# Daughter_Board.net
KiCad netlist of a schematic drawn in EAGLE
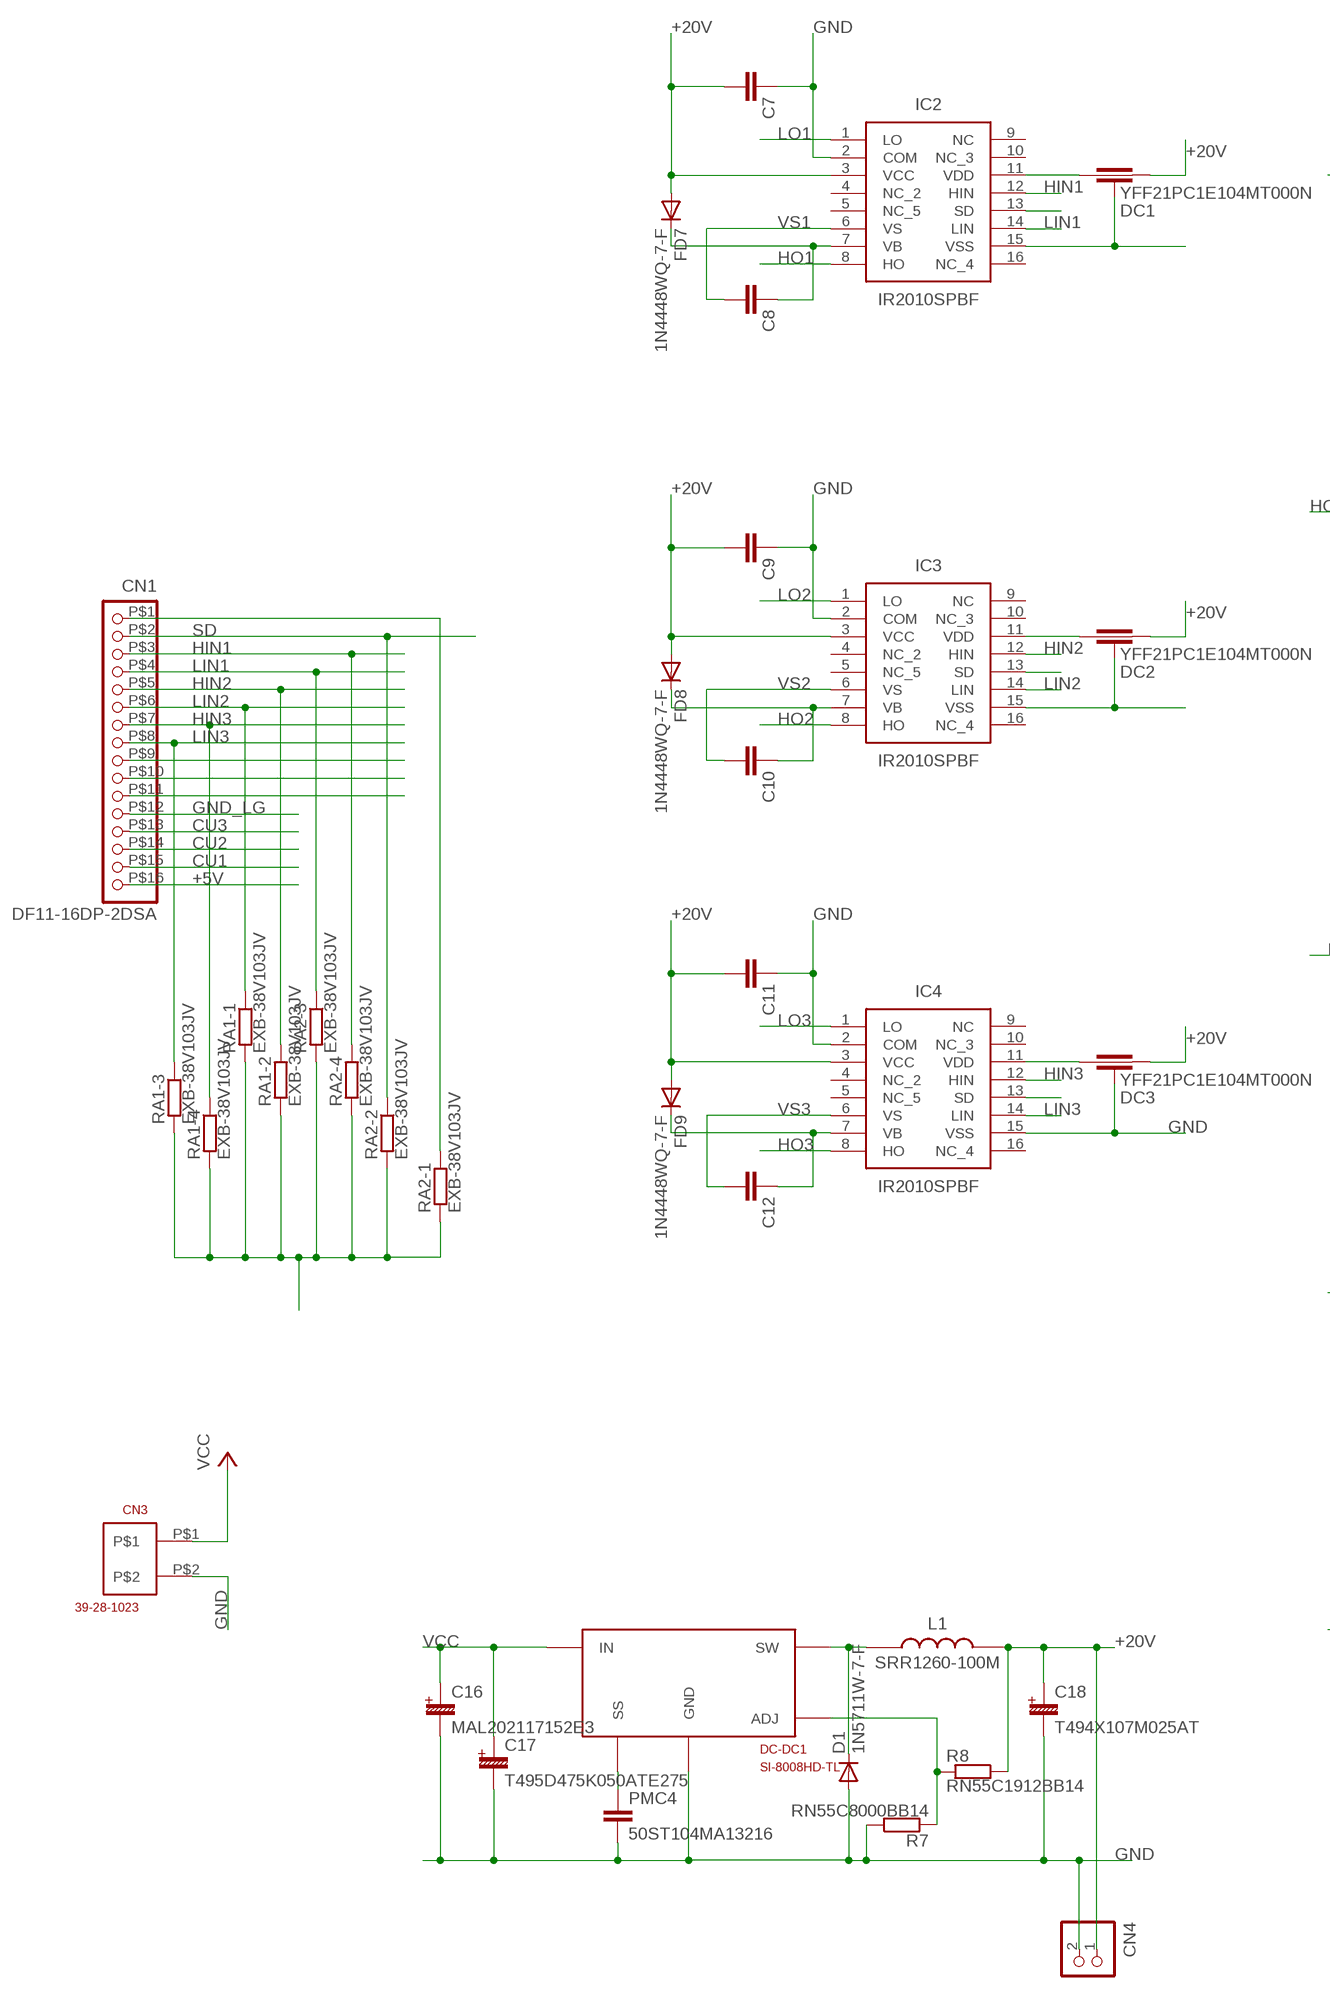
[diagram p0: schematic, sheet 1, part 1 of 3]
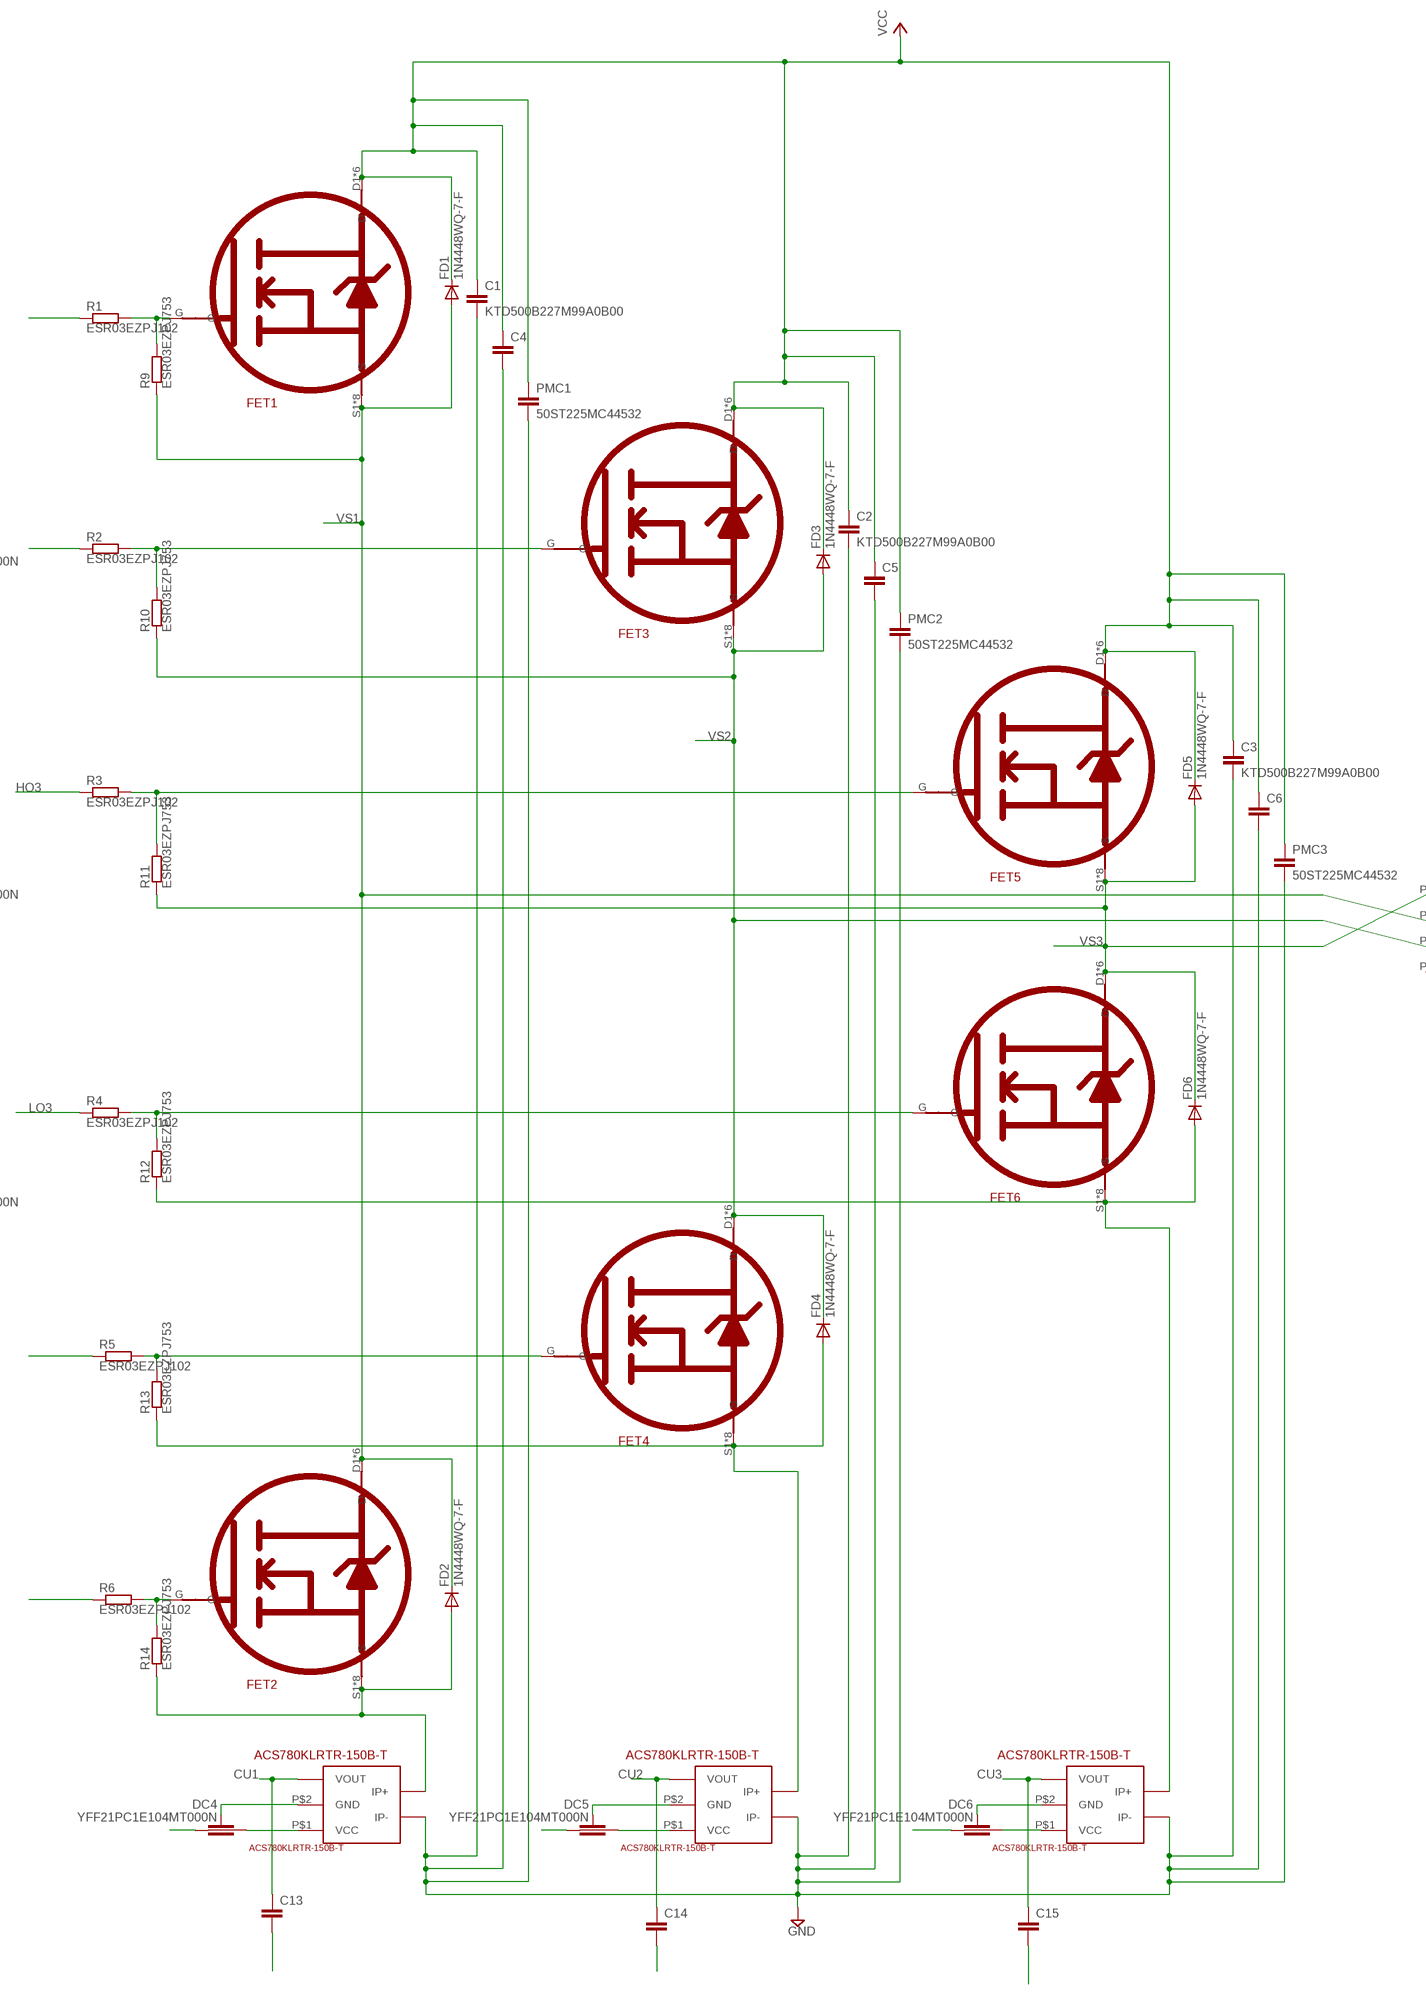
[diagram p1: schematic, sheet 1, part 2 of 3]
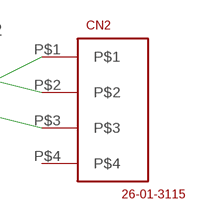
[diagram p2: schematic, sheet 1, part 3 of 3]

(export (version "E")
  (design (tool "Eeschema 10.0.6"))
  (components
    (comp (ref "C1")
      (value "KTD500B227M99A0B00")
      (footprint "eagle-import:TKA50V_150U-220")
      (libsource (lib "eagle-import") (part "KTD500B227M99A0B00"))
    )
    (comp (ref "C2")
      (value "KTD500B227M99A0B00")
      (footprint "eagle-import:TKA50V_150U-220")
      (libsource (lib "eagle-import") (part "KTD500B227M99A0B00"))
    )
    (comp (ref "C3")
      (value "KTD500B227M99A0B00")
      (footprint "eagle-import:TKA50V_150U-220")
      (libsource (lib "eagle-import") (part "KTD500B227M99A0B00"))
    )
    (comp (ref "C4")
      (value "CKG32KX7R1H105M335AJ")
      (footprint "eagle-import:CGK32K")
      (libsource (lib "eagle-import") (part "CKG32KX7R1H105M335AJ"))
    )
    (comp (ref "C5")
      (value "CKG32KX7R1H105M335AJ")
      (footprint "eagle-import:CGK32K")
      (libsource (lib "eagle-import") (part "CKG32KX7R1H105M335AJ"))
    )
    (comp (ref "C6")
      (value "CKG32KX7R1H105M335AJ")
      (footprint "eagle-import:CGK32K")
      (libsource (lib "eagle-import") (part "CKG32KX7R1H105M335AJ"))
    )
    (comp (ref "C7")
      (value "C2012JB0J476M125AC")
      (footprint "eagle-import:C2012")
      (libsource (lib "eagle-import") (part "C2012JB0J476M125AC"))
    )
    (comp (ref "C8")
      (value "C2012JB0J476M125AC")
      (footprint "eagle-import:C2012")
      (libsource (lib "eagle-import") (part "C2012JB0J476M125AC"))
    )
    (comp (ref "C9")
      (value "C2012JB0J476M125AC")
      (footprint "eagle-import:C2012")
      (libsource (lib "eagle-import") (part "C2012JB0J476M125AC"))
    )
    (comp (ref "C10")
      (value "C2012JB0J476M125AC")
      (footprint "eagle-import:C2012")
      (libsource (lib "eagle-import") (part "C2012JB0J476M125AC"))
    )
    (comp (ref "C11")
      (value "C2012JB0J476M125AC")
      (footprint "eagle-import:C2012")
      (libsource (lib "eagle-import") (part "C2012JB0J476M125AC"))
    )
    (comp (ref "C12")
      (value "C2012JB0J476M125AC")
      (footprint "eagle-import:C2012")
      (libsource (lib "eagle-import") (part "C2012JB0J476M125AC"))
    )
    (comp (ref "C13")
      (value "CGA1A2C0G1E180J030BA")
      (footprint "eagle-import:CC0603")
      (libsource (lib "eagle-import") (part "CGA1A2C0G1E180J030BA"))
    )
    (comp (ref "C14")
      (value "CGA1A2C0G1E180J030BA")
      (footprint "eagle-import:CC0603")
      (libsource (lib "eagle-import") (part "CGA1A2C0G1E180J030BA"))
    )
    (comp (ref "C15")
      (value "CGA1A2C0G1E180J030BA")
      (footprint "eagle-import:CC0603")
      (libsource (lib "eagle-import") (part "CGA1A2C0G1E180J030BA"))
    )
    (comp (ref "C16")
      (value "MAL202117152E3")
      (footprint "eagle-import:012AMS13_30")
      (libsource (lib "eagle-import") (part "MAL202117152E3"))
    )
    (comp (ref "C17")
      (value "T495D475K050ATE275")
      (footprint "eagle-import:T495_D")
      (libsource (lib "eagle-import") (part "T495D475K050ATE275"))
    )
    (comp (ref "C18")
      (value "T494X107M025AT")
      (footprint "eagle-import:T494_X")
      (libsource (lib "eagle-import") (part "T494X107M025AT"))
    )
    (comp (ref "CN1")
      (value "DF11-16DP-2DSA")
      (footprint "eagle-import:DF11-16DP-2D")
      (libsource (lib "eagle-import") (part "DF11-16DP-2DSA"))
    )
    (comp (ref "CN2")
      (value "26-01-3115")
      (footprint "eagle-import:26-01-3115")
      (libsource (lib "eagle-import") (part "26-01-3115"))
    )
    (comp (ref "CN3")
      (value "39-28-1023")
      (footprint "eagle-import:39-28-1023")
      (libsource (lib "eagle-import") (part "39-28-1023"))
    )
    (comp (ref "CN4")
      (value "B2B-XH-A")
      (footprint "eagle-import:B2B-XH-A")
      (libsource (lib "eagle-import") (part "B2B-XH-A"))
    )
    (comp (ref "D1")
      (value "1N5711W-7-F")
      (footprint "eagle-import:SOD123")
      (libsource (lib "eagle-import") (part "1N5711W-7-F"))
    )
    (comp (ref "DC-DC1")
      (value "SI-8008HD-TL")
      (footprint "eagle-import:D2_PACAGE_5PIN")
      (libsource (lib "eagle-import") (part "SI-8008HD-TL"))
    )
    (comp (ref "DC1")
      (value "YFF21PC1E104MT000N")
      (footprint "eagle-import:YFF21PC")
      (libsource (lib "eagle-import") (part "YFF21PC1E104MT000N"))
    )
    (comp (ref "DC2")
      (value "YFF21PC1E104MT000N")
      (footprint "eagle-import:YFF21PC")
      (libsource (lib "eagle-import") (part "YFF21PC1E104MT000N"))
    )
    (comp (ref "DC3")
      (value "YFF21PC1E104MT000N")
      (footprint "eagle-import:YFF21PC")
      (libsource (lib "eagle-import") (part "YFF21PC1E104MT000N"))
    )
    (comp (ref "DC4")
      (value "YFF21PC1E104MT000N")
      (footprint "eagle-import:YFF21PC")
      (libsource (lib "eagle-import") (part "YFF21PC1E104MT000N"))
    )
    (comp (ref "DC5")
      (value "YFF21PC1E104MT000N")
      (footprint "eagle-import:YFF21PC")
      (libsource (lib "eagle-import") (part "YFF21PC1E104MT000N"))
    )
    (comp (ref "DC6")
      (value "YFF21PC1E104MT000N")
      (footprint "eagle-import:YFF21PC")
      (libsource (lib "eagle-import") (part "YFF21PC1E104MT000N"))
    )
    (comp (ref "FD1")
      (value "1N4448WQ-7-F")
      (footprint "eagle-import:SOD123")
      (libsource (lib "eagle-import") (part "1N4448WQ-7-F"))
    )
    (comp (ref "FD2")
      (value "1N4448WQ-7-F")
      (footprint "eagle-import:SOD123")
      (libsource (lib "eagle-import") (part "1N4448WQ-7-F"))
    )
    (comp (ref "FD3")
      (value "1N4448WQ-7-F")
      (footprint "eagle-import:SOD123")
      (libsource (lib "eagle-import") (part "1N4448WQ-7-F"))
    )
    (comp (ref "FD4")
      (value "1N4448WQ-7-F")
      (footprint "eagle-import:SOD123")
      (libsource (lib "eagle-import") (part "1N4448WQ-7-F"))
    )
    (comp (ref "FD5")
      (value "1N4448WQ-7-F")
      (footprint "eagle-import:SOD123")
      (libsource (lib "eagle-import") (part "1N4448WQ-7-F"))
    )
    (comp (ref "FD6")
      (value "1N4448WQ-7-F")
      (footprint "eagle-import:SOD123")
      (libsource (lib "eagle-import") (part "1N4448WQ-7-F"))
    )
    (comp (ref "FD7")
      (value "1N4448WQ-7-F")
      (footprint "eagle-import:SOD123")
      (libsource (lib "eagle-import") (part "1N4448WQ-7-F"))
    )
    (comp (ref "FD8")
      (value "1N4448WQ-7-F")
      (footprint "eagle-import:SOD123")
      (libsource (lib "eagle-import") (part "1N4448WQ-7-F"))
    )
    (comp (ref "FD9")
      (value "1N4448WQ-7-F")
      (footprint "eagle-import:SOD123")
      (libsource (lib "eagle-import") (part "1N4448WQ-7-F"))
    )
    (comp (ref "FET1")
      (value "IRF7739L1TRPBF")
      (footprint "eagle-import:DIRECT_FET-L8")
      (libsource (lib "eagle-import") (part "IRF7739L1TRPBF"))
    )
    (comp (ref "FET2")
      (value "IRF7739L1TRPBF")
      (footprint "eagle-import:DIRECT_FET-L8")
      (libsource (lib "eagle-import") (part "IRF7739L1TRPBF"))
    )
    (comp (ref "FET3")
      (value "IRF7739L1TRPBF")
      (footprint "eagle-import:DIRECT_FET-L8")
      (libsource (lib "eagle-import") (part "IRF7739L1TRPBF"))
    )
    (comp (ref "FET4")
      (value "IRF7739L1TRPBF")
      (footprint "eagle-import:DIRECT_FET-L8")
      (libsource (lib "eagle-import") (part "IRF7739L1TRPBF"))
    )
    (comp (ref "FET5")
      (value "IRF7739L1TRPBF")
      (footprint "eagle-import:DIRECT_FET-L8")
      (libsource (lib "eagle-import") (part "IRF7739L1TRPBF"))
    )
    (comp (ref "FET6")
      (value "IRF7739L1TRPBF")
      (footprint "eagle-import:DIRECT_FET-L8")
      (libsource (lib "eagle-import") (part "IRF7739L1TRPBF"))
    )
    (comp (ref "IC1")
      (value "ACS780KLRTR-150B-T")
      (footprint "eagle-import:7-PIN_PSOP")
      (libsource (lib "eagle-import") (part "ACS780KLRTR-150B-T"))
    )
    (comp (ref "IC2")
      (value "IR2010SPBF")
      (footprint "eagle-import:SOIC127P1032X265-16N")
      (fields (field (name "RS_PART_NUMBER") "2509056226"))
      (libsource (lib "eagle-import") (part "IR2010SPBF"))
    )
    (comp (ref "IC3")
      (value "IR2010SPBF")
      (footprint "eagle-import:SOIC127P1032X265-16N")
      (fields (field (name "RS_PART_NUMBER") "2509056226"))
      (libsource (lib "eagle-import") (part "IR2010SPBF"))
    )
    (comp (ref "IC4")
      (value "IR2010SPBF")
      (footprint "eagle-import:SOIC127P1032X265-16N")
      (fields (field (name "RS_PART_NUMBER") "2509056226"))
      (libsource (lib "eagle-import") (part "IR2010SPBF"))
    )
    (comp (ref "IC5")
      (value "ACS780KLRTR-150B-T")
      (footprint "eagle-import:7-PIN_PSOP")
      (libsource (lib "eagle-import") (part "ACS780KLRTR-150B-T"))
    )
    (comp (ref "IC6")
      (value "ACS780KLRTR-150B-T")
      (footprint "eagle-import:7-PIN_PSOP")
      (libsource (lib "eagle-import") (part "ACS780KLRTR-150B-T"))
    )
    (comp (ref "L1")
      (value "SRR1260-100M")
      (footprint "eagle-import:SRR1260")
      (libsource (lib "eagle-import") (part "SRR1260-100M"))
    )
    (comp (ref "PMC1")
      (value "50ST225MC44532")
      (footprint "eagle-import:4532")
      (libsource (lib "eagle-import") (part "50ST225MC44532"))
    )
    (comp (ref "PMC2")
      (value "50ST225MC44532")
      (footprint "eagle-import:4532")
      (libsource (lib "eagle-import") (part "50ST225MC44532"))
    )
    (comp (ref "PMC3")
      (value "50ST225MC44532")
      (footprint "eagle-import:4532")
      (libsource (lib "eagle-import") (part "50ST225MC44532"))
    )
    (comp (ref "PMC4")
      (value "50ST104MA13216")
      (footprint "eagle-import:3216")
      (libsource (lib "eagle-import") (part "50ST104MA13216"))
    )
    (comp (ref "R1")
      (value "ESR03EZPJ102")
      (footprint "eagle-import:ESR03")
      (libsource (lib "eagle-import") (part "ESR03EZPJ102"))
    )
    (comp (ref "R2")
      (value "ESR03EZPJ102")
      (footprint "eagle-import:ESR03")
      (libsource (lib "eagle-import") (part "ESR03EZPJ102"))
    )
    (comp (ref "R3")
      (value "ESR03EZPJ102")
      (footprint "eagle-import:ESR03")
      (libsource (lib "eagle-import") (part "ESR03EZPJ102"))
    )
    (comp (ref "R4")
      (value "ESR03EZPJ102")
      (footprint "eagle-import:ESR03")
      (libsource (lib "eagle-import") (part "ESR03EZPJ102"))
    )
    (comp (ref "R5")
      (value "ESR03EZPJ102")
      (footprint "eagle-import:ESR03")
      (libsource (lib "eagle-import") (part "ESR03EZPJ102"))
    )
    (comp (ref "R6")
      (value "ESR03EZPJ102")
      (footprint "eagle-import:ESR03")
      (libsource (lib "eagle-import") (part "ESR03EZPJ102"))
    )
    (comp (ref "R7")
      (value "RN55C8000BB14")
      (footprint "eagle-import:CMF55")
      (libsource (lib "eagle-import") (part "RN55C8000BB14"))
    )
    (comp (ref "R8")
      (value "RN55C1912BB14")
      (footprint "eagle-import:CMF55")
      (libsource (lib "eagle-import") (part "RN55C1912BB14"))
    )
    (comp (ref "R9")
      (value "ESR03EZPJ753")
      (footprint "eagle-import:ESR03")
      (libsource (lib "eagle-import") (part "ESR03EZPJ753"))
    )
    (comp (ref "R10")
      (value "ESR03EZPJ753")
      (footprint "eagle-import:ESR03")
      (libsource (lib "eagle-import") (part "ESR03EZPJ753"))
    )
    (comp (ref "R11")
      (value "ESR03EZPJ753")
      (footprint "eagle-import:ESR03")
      (libsource (lib "eagle-import") (part "ESR03EZPJ753"))
    )
    (comp (ref "R12")
      (value "ESR03EZPJ753")
      (footprint "eagle-import:ESR03")
      (libsource (lib "eagle-import") (part "ESR03EZPJ753"))
    )
    (comp (ref "R13")
      (value "ESR03EZPJ753")
      (footprint "eagle-import:ESR03")
      (libsource (lib "eagle-import") (part "ESR03EZPJ753"))
    )
    (comp (ref "R14")
      (value "ESR03EZPJ753")
      (footprint "eagle-import:ESR03")
      (libsource (lib "eagle-import") (part "ESR03EZPJ753"))
    )
    (comp (ref "RA1")
      (value "EXB-38V103JV")
      (footprint "eagle-import:EXB-38V,28V")
      (libsource (lib "eagle-import") (part "EXB-38V103JV"))
    )
    (comp (ref "RA2")
      (value "EXB-38V103JV")
      (footprint "eagle-import:EXB-38V,28V")
      (libsource (lib "eagle-import") (part "EXB-38V103JV"))
    )
  )
  (nets
    (net (code "1") (name "/+5V") (class "Default")
      (node (ref "CN1") (pin "P$16") (pinfunction "16_P$16") (pintype "passive"))
      (node (ref "DC4") (pin "P$2") (pinfunction "P$2_P$2") (pintype "bidirectional"))
      (node (ref "DC5") (pin "P$2") (pinfunction "P$2_P$2") (pintype "bidirectional"))
      (node (ref "DC6") (pin "P$2") (pinfunction "P$2_P$2") (pintype "bidirectional"))
    )
    (net (code "2") (name "/+20V") (class "Default")
      (node (ref "C11") (pin "P$2") (pinfunction "2_P$2") (pintype "passive"))
      (node (ref "C18") (pin "P$+") (pinfunction "+_P$+") (pintype "passive"))
      (node (ref "C7") (pin "P$2") (pinfunction "2_P$2") (pintype "passive"))
      (node (ref "C9") (pin "P$2") (pinfunction "2_P$2") (pintype "passive"))
      (node (ref "CN4") (pin "1") (pinfunction "1_1") (pintype "passive"))
      (node (ref "DC1") (pin "P$2") (pinfunction "P$2_P$2") (pintype "bidirectional"))
      (node (ref "DC2") (pin "P$2") (pinfunction "P$2_P$2") (pintype "bidirectional"))
      (node (ref "DC3") (pin "P$2") (pinfunction "P$2_P$2") (pintype "bidirectional"))
      (node (ref "FD7") (pin "A") (pinfunction "A_A") (pintype "passive"))
      (node (ref "FD8") (pin "A") (pinfunction "A_A") (pintype "passive"))
      (node (ref "FD9") (pin "A") (pinfunction "A_A") (pintype "passive"))
      (node (ref "IC2") (pin "3") (pinfunction "VCC_3") (pintype "passive"))
      (node (ref "IC3") (pin "3") (pinfunction "VCC_3") (pintype "passive"))
      (node (ref "IC4") (pin "3") (pinfunction "VCC_3") (pintype "passive"))
      (node (ref "L1") (pin "P$2") (pinfunction "2_P$2") (pintype "bidirectional"))
      (node (ref "R8") (pin "P$1") (pinfunction "1_P$1") (pintype "passive"))
    )
    (net (code "3") (name "/CU1") (class "Default")
      (node (ref "C13") (pin "P$1") (pinfunction "1_P$1") (pintype "passive"))
      (node (ref "CN1") (pin "P$15") (pinfunction "15_P$15") (pintype "passive"))
      (node (ref "IC1") (pin "P$3") (pinfunction "VOUT_P$3") (pintype "bidirectional"))
    )
    (net (code "4") (name "/CU2") (class "Default")
      (node (ref "C14") (pin "P$1") (pinfunction "1_P$1") (pintype "passive"))
      (node (ref "CN1") (pin "P$14") (pinfunction "14_P$14") (pintype "passive"))
      (node (ref "IC5") (pin "P$3") (pinfunction "VOUT_P$3") (pintype "bidirectional"))
    )
    (net (code "5") (name "/CU3") (class "Default")
      (node (ref "C15") (pin "P$1") (pinfunction "1_P$1") (pintype "passive"))
      (node (ref "CN1") (pin "P$13") (pinfunction "13_P$13") (pintype "passive"))
      (node (ref "IC6") (pin "P$3") (pinfunction "VOUT_P$3") (pintype "bidirectional"))
    )
    (net (code "6") (name "/GND_LG") (class "Default")
      (node (ref "C13") (pin "P$2") (pinfunction "2_P$2") (pintype "passive"))
      (node (ref "C14") (pin "P$2") (pinfunction "2_P$2") (pintype "passive"))
      (node (ref "C15") (pin "P$2") (pinfunction "2_P$2") (pintype "passive"))
      (node (ref "CN1") (pin "P$12") (pinfunction "12_P$12") (pintype "passive"))
      (node (ref "DC4") (pin "GND1") (pinfunction "GND_GND1") (pintype "bidirectional"))
      (node (ref "DC4") (pin "GND2") (pinfunction "GND_GND2") (pintype "bidirectional"))
      (node (ref "DC5") (pin "GND1") (pinfunction "GND_GND1") (pintype "bidirectional"))
      (node (ref "DC5") (pin "GND2") (pinfunction "GND_GND2") (pintype "bidirectional"))
      (node (ref "DC6") (pin "GND1") (pinfunction "GND_GND1") (pintype "bidirectional"))
      (node (ref "DC6") (pin "GND2") (pinfunction "GND_GND2") (pintype "bidirectional"))
      (node (ref "IC1") (pin "P$2") (pinfunction "GND_P$2") (pintype "bidirectional"))
      (node (ref "IC5") (pin "P$2") (pinfunction "GND_P$2") (pintype "bidirectional"))
      (node (ref "IC6") (pin "P$2") (pinfunction "GND_P$2") (pintype "bidirectional"))
      (node (ref "RA1") (pin "P$5") (pinfunction "2_P$5") (pintype "passive"))
      (node (ref "RA1") (pin "P$6") (pinfunction "2_P$6") (pintype "passive"))
      (node (ref "RA1") (pin "P$7") (pinfunction "2_P$7") (pintype "passive"))
      (node (ref "RA1") (pin "P$8") (pinfunction "2_P$8") (pintype "passive"))
      (node (ref "RA2") (pin "P$5") (pinfunction "2_P$5") (pintype "passive"))
      (node (ref "RA2") (pin "P$6") (pinfunction "2_P$6") (pintype "passive"))
      (node (ref "RA2") (pin "P$7") (pinfunction "2_P$7") (pintype "passive"))
      (node (ref "RA2") (pin "P$8") (pinfunction "2_P$8") (pintype "passive"))
    )
    (net (code "7") (name "/HIN1") (class "Default")
      (node (ref "CN1") (pin "P$3") (pinfunction "3_P$3") (pintype "passive"))
      (node (ref "IC2") (pin "12") (pinfunction "HIN_12") (pintype "passive"))
      (node (ref "RA2") (pin "P$4") (pinfunction "1_P$4") (pintype "passive"))
    )
    (net (code "8") (name "/HIN2") (class "Default")
      (node (ref "CN1") (pin "P$5") (pinfunction "5_P$5") (pintype "passive"))
      (node (ref "IC3") (pin "12") (pinfunction "HIN_12") (pintype "passive"))
      (node (ref "RA1") (pin "P$2") (pinfunction "1_P$2") (pintype "passive"))
    )
    (net (code "9") (name "/HIN3") (class "Default")
      (node (ref "CN1") (pin "P$7") (pinfunction "7_P$7") (pintype "passive"))
      (node (ref "IC4") (pin "12") (pinfunction "HIN_12") (pintype "passive"))
      (node (ref "RA1") (pin "P$4") (pinfunction "1_P$4") (pintype "passive"))
    )
    (net (code "10") (name "/HO1") (class "Default")
      (node (ref "IC2") (pin "8") (pinfunction "HO_8") (pintype "passive"))
      (node (ref "R1") (pin "P$2") (pinfunction "2_P$2") (pintype "passive"))
    )
    (net (code "11") (name "/HO2") (class "Default")
      (node (ref "IC3") (pin "8") (pinfunction "HO_8") (pintype "passive"))
      (node (ref "R2") (pin "P$2") (pinfunction "2_P$2") (pintype "passive"))
    )
    (net (code "12") (name "/HO3") (class "Default")
      (node (ref "IC4") (pin "8") (pinfunction "HO_8") (pintype "passive"))
      (node (ref "R3") (pin "P$2") (pinfunction "2_P$2") (pintype "passive"))
    )
    (net (code "13") (name "/LIN1") (class "Default")
      (node (ref "CN1") (pin "P$4") (pinfunction "4_P$4") (pintype "passive"))
      (node (ref "IC2") (pin "14") (pinfunction "LIN_14") (pintype "passive"))
      (node (ref "RA2") (pin "P$3") (pinfunction "1_P$3") (pintype "passive"))
    )
    (net (code "14") (name "/LIN2") (class "Default")
      (node (ref "CN1") (pin "P$6") (pinfunction "6_P$6") (pintype "passive"))
      (node (ref "IC3") (pin "14") (pinfunction "LIN_14") (pintype "passive"))
      (node (ref "RA1") (pin "P$1") (pinfunction "1_P$1") (pintype "passive"))
    )
    (net (code "15") (name "/LIN3") (class "Default")
      (node (ref "CN1") (pin "P$8") (pinfunction "8_P$8") (pintype "passive"))
      (node (ref "IC4") (pin "14") (pinfunction "LIN_14") (pintype "passive"))
      (node (ref "RA1") (pin "P$3") (pinfunction "1_P$3") (pintype "passive"))
    )
    (net (code "16") (name "/LO1") (class "Default")
      (node (ref "IC2") (pin "1") (pinfunction "LO_1") (pintype "passive"))
      (node (ref "R6") (pin "P$2") (pinfunction "2_P$2") (pintype "passive"))
    )
    (net (code "17") (name "/LO2") (class "Default")
      (node (ref "IC3") (pin "1") (pinfunction "LO_1") (pintype "passive"))
      (node (ref "R5") (pin "P$2") (pinfunction "2_P$2") (pintype "passive"))
    )
    (net (code "18") (name "/LO3") (class "Default")
      (node (ref "IC4") (pin "1") (pinfunction "LO_1") (pintype "passive"))
      (node (ref "R4") (pin "P$2") (pinfunction "2_P$2") (pintype "passive"))
    )
    (net (code "19") (name "/SD") (class "Default")
      (node (ref "CN1") (pin "P$2") (pinfunction "2_P$2") (pintype "passive"))
      (node (ref "IC2") (pin "13") (pinfunction "SD_13") (pintype "passive"))
      (node (ref "IC3") (pin "13") (pinfunction "SD_13") (pintype "passive"))
      (node (ref "IC4") (pin "13") (pinfunction "SD_13") (pintype "passive"))
      (node (ref "RA2") (pin "P$2") (pinfunction "1_P$2") (pintype "passive"))
    )
    (net (code "20") (name "/VS1") (class "Default")
      (node (ref "C8") (pin "P$2") (pinfunction "2_P$2") (pintype "passive"))
      (node (ref "CN2") (pin "P$2") (pinfunction "P$2_P$2") (pintype "bidirectional"))
      (node (ref "FD1") (pin "A") (pinfunction "A_A") (pintype "passive"))
      (node (ref "FD2") (pin "K") (pinfunction "C_K") (pintype "passive"))
      (node (ref "FET1") (pin "S1") (pinfunction "S_S1") (pintype "bidirectional"))
      (node (ref "FET1") (pin "S2") (pinfunction "S_S2") (pintype "bidirectional"))
      (node (ref "FET1") (pin "S3") (pinfunction "S_S3") (pintype "bidirectional"))
      (node (ref "FET1") (pin "S4") (pinfunction "S_S4") (pintype "bidirectional"))
      (node (ref "FET1") (pin "S5") (pinfunction "S_S5") (pintype "bidirectional"))
      (node (ref "FET1") (pin "S6") (pinfunction "S_S6") (pintype "bidirectional"))
      (node (ref "FET1") (pin "S7") (pinfunction "S_S7") (pintype "bidirectional"))
      (node (ref "FET1") (pin "S8") (pinfunction "S_S8") (pintype "bidirectional"))
      (node (ref "FET2") (pin "D1") (pinfunction "D_D1") (pintype "bidirectional"))
      (node (ref "FET2") (pin "D2") (pinfunction "D_D2") (pintype "bidirectional"))
      (node (ref "FET2") (pin "D3") (pinfunction "D_D3") (pintype "bidirectional"))
      (node (ref "FET2") (pin "D4") (pinfunction "D_D4") (pintype "bidirectional"))
      (node (ref "FET2") (pin "D5") (pinfunction "D_D5") (pintype "bidirectional"))
      (node (ref "FET2") (pin "D6") (pinfunction "D_D6") (pintype "bidirectional"))
      (node (ref "IC2") (pin "6") (pinfunction "VS_6") (pintype "passive"))
      (node (ref "R9") (pin "P$2") (pinfunction "2_P$2") (pintype "passive"))
    )
    (net (code "21") (name "/VS2") (class "Default")
      (node (ref "C10") (pin "P$2") (pinfunction "2_P$2") (pintype "passive"))
      (node (ref "CN2") (pin "P$3") (pinfunction "P$3_P$3") (pintype "bidirectional"))
      (node (ref "FD3") (pin "A") (pinfunction "A_A") (pintype "passive"))
      (node (ref "FD4") (pin "K") (pinfunction "C_K") (pintype "passive"))
      (node (ref "FET3") (pin "S1") (pinfunction "S_S1") (pintype "bidirectional"))
      (node (ref "FET3") (pin "S2") (pinfunction "S_S2") (pintype "bidirectional"))
      (node (ref "FET3") (pin "S3") (pinfunction "S_S3") (pintype "bidirectional"))
      (node (ref "FET3") (pin "S4") (pinfunction "S_S4") (pintype "bidirectional"))
      (node (ref "FET3") (pin "S5") (pinfunction "S_S5") (pintype "bidirectional"))
      (node (ref "FET3") (pin "S6") (pinfunction "S_S6") (pintype "bidirectional"))
      (node (ref "FET3") (pin "S7") (pinfunction "S_S7") (pintype "bidirectional"))
      (node (ref "FET3") (pin "S8") (pinfunction "S_S8") (pintype "bidirectional"))
      (node (ref "FET4") (pin "D1") (pinfunction "D_D1") (pintype "bidirectional"))
      (node (ref "FET4") (pin "D2") (pinfunction "D_D2") (pintype "bidirectional"))
      (node (ref "FET4") (pin "D3") (pinfunction "D_D3") (pintype "bidirectional"))
      (node (ref "FET4") (pin "D4") (pinfunction "D_D4") (pintype "bidirectional"))
      (node (ref "FET4") (pin "D5") (pinfunction "D_D5") (pintype "bidirectional"))
      (node (ref "FET4") (pin "D6") (pinfunction "D_D6") (pintype "bidirectional"))
      (node (ref "IC3") (pin "6") (pinfunction "VS_6") (pintype "passive"))
      (node (ref "R10") (pin "P$2") (pinfunction "2_P$2") (pintype "passive"))
    )
    (net (code "22") (name "/VS3") (class "Default")
      (node (ref "C12") (pin "P$2") (pinfunction "2_P$2") (pintype "passive"))
      (node (ref "CN2") (pin "P$1") (pinfunction "P$1_P$1") (pintype "bidirectional"))
      (node (ref "FD5") (pin "A") (pinfunction "A_A") (pintype "passive"))
      (node (ref "FD6") (pin "K") (pinfunction "C_K") (pintype "passive"))
      (node (ref "FET5") (pin "S1") (pinfunction "S_S1") (pintype "bidirectional"))
      (node (ref "FET5") (pin "S2") (pinfunction "S_S2") (pintype "bidirectional"))
      (node (ref "FET5") (pin "S3") (pinfunction "S_S3") (pintype "bidirectional"))
      (node (ref "FET5") (pin "S4") (pinfunction "S_S4") (pintype "bidirectional"))
      (node (ref "FET5") (pin "S5") (pinfunction "S_S5") (pintype "bidirectional"))
      (node (ref "FET5") (pin "S6") (pinfunction "S_S6") (pintype "bidirectional"))
      (node (ref "FET5") (pin "S7") (pinfunction "S_S7") (pintype "bidirectional"))
      (node (ref "FET5") (pin "S8") (pinfunction "S_S8") (pintype "bidirectional"))
      (node (ref "FET6") (pin "D1") (pinfunction "D_D1") (pintype "bidirectional"))
      (node (ref "FET6") (pin "D2") (pinfunction "D_D2") (pintype "bidirectional"))
      (node (ref "FET6") (pin "D3") (pinfunction "D_D3") (pintype "bidirectional"))
      (node (ref "FET6") (pin "D4") (pinfunction "D_D4") (pintype "bidirectional"))
      (node (ref "FET6") (pin "D5") (pinfunction "D_D5") (pintype "bidirectional"))
      (node (ref "FET6") (pin "D6") (pinfunction "D_D6") (pintype "bidirectional"))
      (node (ref "IC4") (pin "6") (pinfunction "VS_6") (pintype "passive"))
      (node (ref "R11") (pin "P$2") (pinfunction "2_P$2") (pintype "passive"))
    )
    (net (code "23") (name "GND") (class "Default")
      (node (ref "C1") (pin "P$2") (pinfunction "2_P$2") (pintype "passive"))
      (node (ref "C11") (pin "P$1") (pinfunction "1_P$1") (pintype "passive"))
      (node (ref "C16") (pin "P$2") (pinfunction "2_P$2") (pintype "passive"))
      (node (ref "C17") (pin "P$2") (pinfunction "2_P$2") (pintype "passive"))
      (node (ref "C18") (pin "P$2") (pinfunction "2_P$2") (pintype "passive"))
      (node (ref "C2") (pin "P$2") (pinfunction "2_P$2") (pintype "passive"))
      (node (ref "C3") (pin "P$2") (pinfunction "2_P$2") (pintype "passive"))
      (node (ref "C4") (pin "P$2") (pinfunction "2_P$2") (pintype "passive"))
      (node (ref "C5") (pin "P$2") (pinfunction "2_P$2") (pintype "passive"))
      (node (ref "C6") (pin "P$2") (pinfunction "2_P$2") (pintype "passive"))
      (node (ref "C7") (pin "P$1") (pinfunction "1_P$1") (pintype "passive"))
      (node (ref "C9") (pin "P$1") (pinfunction "1_P$1") (pintype "passive"))
      (node (ref "CN3") (pin "P$2") (pinfunction "P$2_P$2") (pintype "bidirectional"))
      (node (ref "CN4") (pin "2") (pinfunction "2_2") (pintype "passive"))
      (node (ref "D1") (pin "A") (pinfunction "A_A") (pintype "passive"))
      (node (ref "DC-DC1") (pin "P$1") (pinfunction "GND_P$1") (pintype "bidirectional"))
      (node (ref "DC-DC1") (pin "P$4") (pinfunction "GND_P$4") (pintype "bidirectional"))
      (node (ref "DC1") (pin "GND1") (pinfunction "GND_GND1") (pintype "bidirectional"))
      (node (ref "DC1") (pin "GND2") (pinfunction "GND_GND2") (pintype "bidirectional"))
      (node (ref "DC2") (pin "GND1") (pinfunction "GND_GND1") (pintype "bidirectional"))
      (node (ref "DC2") (pin "GND2") (pinfunction "GND_GND2") (pintype "bidirectional"))
      (node (ref "DC3") (pin "GND1") (pinfunction "GND_GND1") (pintype "bidirectional"))
      (node (ref "DC3") (pin "GND2") (pinfunction "GND_GND2") (pintype "bidirectional"))
      (node (ref "IC1") (pin "P$6") (pinfunction "IP-_P$6") (pintype "bidirectional"))
      (node (ref "IC2") (pin "15") (pinfunction "VSS_15") (pintype "passive"))
      (node (ref "IC2") (pin "2") (pinfunction "COM_2") (pintype "passive"))
      (node (ref "IC3") (pin "15") (pinfunction "VSS_15") (pintype "passive"))
      (node (ref "IC3") (pin "2") (pinfunction "COM_2") (pintype "passive"))
      (node (ref "IC4") (pin "15") (pinfunction "VSS_15") (pintype "passive"))
      (node (ref "IC4") (pin "2") (pinfunction "COM_2") (pintype "passive"))
      (node (ref "IC5") (pin "P$6") (pinfunction "IP-_P$6") (pintype "bidirectional"))
      (node (ref "IC6") (pin "P$6") (pinfunction "IP-_P$6") (pintype "bidirectional"))
      (node (ref "PMC1") (pin "P$2") (pinfunction "2_P$2") (pintype "passive"))
      (node (ref "PMC2") (pin "P$2") (pinfunction "2_P$2") (pintype "passive"))
      (node (ref "PMC3") (pin "P$2") (pinfunction "2_P$2") (pintype "passive"))
      (node (ref "PMC4") (pin "P$2") (pinfunction "2_P$2") (pintype "passive"))
      (node (ref "R7") (pin "P$1") (pinfunction "1_P$1") (pintype "passive"))
    )
    (net (code "24") (name "Net-(C8-1)") (class "Default")
      (node (ref "C8") (pin "P$1") (pinfunction "1_P$1") (pintype "passive"))
      (node (ref "FD7") (pin "K") (pinfunction "C_K") (pintype "passive"))
      (node (ref "IC2") (pin "7") (pinfunction "VB_7") (pintype "passive"))
    )
    (net (code "25") (name "Net-(C10-1)") (class "Default")
      (node (ref "C10") (pin "P$1") (pinfunction "1_P$1") (pintype "passive"))
      (node (ref "FD8") (pin "K") (pinfunction "C_K") (pintype "passive"))
      (node (ref "IC3") (pin "7") (pinfunction "VB_7") (pintype "passive"))
    )
    (net (code "26") (name "Net-(C12-1)") (class "Default")
      (node (ref "C12") (pin "P$1") (pinfunction "1_P$1") (pintype "passive"))
      (node (ref "FD9") (pin "K") (pinfunction "C_K") (pintype "passive"))
      (node (ref "IC4") (pin "7") (pinfunction "VB_7") (pintype "passive"))
    )
    (net (code "27") (name "Net-(CN1-1)") (class "Default")
      (node (ref "CN1") (pin "P$1") (pinfunction "1_P$1") (pintype "passive"))
      (node (ref "RA2") (pin "P$1") (pinfunction "1_P$1") (pintype "passive"))
    )
    (net (code "28") (name "Net-(D1-C)") (class "Default")
      (node (ref "D1") (pin "K") (pinfunction "C_K") (pintype "passive"))
      (node (ref "DC-DC1") (pin "P$3") (pinfunction "SW_P$3") (pintype "bidirectional"))
      (node (ref "L1") (pin "P$1") (pinfunction "1_P$1") (pintype "bidirectional"))
    )
    (net (code "29") (name "Net-(DC-DC1-ADJ)") (class "Default")
      (node (ref "DC-DC1") (pin "P$5") (pinfunction "ADJ_P$5") (pintype "bidirectional"))
      (node (ref "R7") (pin "P$2") (pinfunction "2_P$2") (pintype "passive"))
      (node (ref "R8") (pin "P$2") (pinfunction "2_P$2") (pintype "passive"))
    )
    (net (code "30") (name "Net-(DC-DC1-SS)") (class "Default")
      (node (ref "DC-DC1") (pin "P$6") (pinfunction "SS_P$6") (pintype "bidirectional"))
      (node (ref "PMC4") (pin "P$1") (pinfunction "1_P$1") (pintype "passive"))
    )
    (net (code "31") (name "Net-(IC1-IP+)") (class "Default")
      (node (ref "FD2") (pin "A") (pinfunction "A_A") (pintype "passive"))
      (node (ref "FET2") (pin "S1") (pinfunction "S_S1") (pintype "bidirectional"))
      (node (ref "FET2") (pin "S2") (pinfunction "S_S2") (pintype "bidirectional"))
      (node (ref "FET2") (pin "S3") (pinfunction "S_S3") (pintype "bidirectional"))
      (node (ref "FET2") (pin "S4") (pinfunction "S_S4") (pintype "bidirectional"))
      (node (ref "FET2") (pin "S5") (pinfunction "S_S5") (pintype "bidirectional"))
      (node (ref "FET2") (pin "S6") (pinfunction "S_S6") (pintype "bidirectional"))
      (node (ref "FET2") (pin "S7") (pinfunction "S_S7") (pintype "bidirectional"))
      (node (ref "FET2") (pin "S8") (pinfunction "S_S8") (pintype "bidirectional"))
      (node (ref "IC1") (pin "P$5") (pinfunction "IP+_P$5") (pintype "bidirectional"))
      (node (ref "R14") (pin "P$2") (pinfunction "2_P$2") (pintype "passive"))
    )
    (net (code "32") (name "Net-(IC1-VCC)") (class "Default")
      (node (ref "DC4") (pin "P$1") (pinfunction "P$1_P$1") (pintype "bidirectional"))
      (node (ref "IC1") (pin "P$1") (pinfunction "VCC_P$1") (pintype "bidirectional"))
    )
    (net (code "33") (name "Net-(IC2-VDD)") (class "Default")
      (node (ref "DC1") (pin "P$1") (pinfunction "P$1_P$1") (pintype "bidirectional"))
      (node (ref "IC2") (pin "11") (pinfunction "VDD_11") (pintype "passive"))
    )
    (net (code "34") (name "Net-(IC3-VDD)") (class "Default")
      (node (ref "DC2") (pin "P$1") (pinfunction "P$1_P$1") (pintype "bidirectional"))
      (node (ref "IC3") (pin "11") (pinfunction "VDD_11") (pintype "passive"))
    )
    (net (code "35") (name "Net-(IC4-VDD)") (class "Default")
      (node (ref "DC3") (pin "P$1") (pinfunction "P$1_P$1") (pintype "bidirectional"))
      (node (ref "IC4") (pin "11") (pinfunction "VDD_11") (pintype "passive"))
    )
    (net (code "36") (name "Net-(IC5-IP+)") (class "Default")
      (node (ref "FD4") (pin "A") (pinfunction "A_A") (pintype "passive"))
      (node (ref "FET4") (pin "S1") (pinfunction "S_S1") (pintype "bidirectional"))
      (node (ref "FET4") (pin "S2") (pinfunction "S_S2") (pintype "bidirectional"))
      (node (ref "FET4") (pin "S3") (pinfunction "S_S3") (pintype "bidirectional"))
      (node (ref "FET4") (pin "S4") (pinfunction "S_S4") (pintype "bidirectional"))
      (node (ref "FET4") (pin "S5") (pinfunction "S_S5") (pintype "bidirectional"))
      (node (ref "FET4") (pin "S6") (pinfunction "S_S6") (pintype "bidirectional"))
      (node (ref "FET4") (pin "S7") (pinfunction "S_S7") (pintype "bidirectional"))
      (node (ref "FET4") (pin "S8") (pinfunction "S_S8") (pintype "bidirectional"))
      (node (ref "IC5") (pin "P$5") (pinfunction "IP+_P$5") (pintype "bidirectional"))
      (node (ref "R13") (pin "P$2") (pinfunction "2_P$2") (pintype "passive"))
    )
    (net (code "37") (name "Net-(IC5-VCC)") (class "Default")
      (node (ref "DC5") (pin "P$1") (pinfunction "P$1_P$1") (pintype "bidirectional"))
      (node (ref "IC5") (pin "P$1") (pinfunction "VCC_P$1") (pintype "bidirectional"))
    )
    (net (code "38") (name "Net-(IC6-IP+)") (class "Default")
      (node (ref "FD6") (pin "A") (pinfunction "A_A") (pintype "passive"))
      (node (ref "FET6") (pin "S1") (pinfunction "S_S1") (pintype "bidirectional"))
      (node (ref "FET6") (pin "S2") (pinfunction "S_S2") (pintype "bidirectional"))
      (node (ref "FET6") (pin "S3") (pinfunction "S_S3") (pintype "bidirectional"))
      (node (ref "FET6") (pin "S4") (pinfunction "S_S4") (pintype "bidirectional"))
      (node (ref "FET6") (pin "S5") (pinfunction "S_S5") (pintype "bidirectional"))
      (node (ref "FET6") (pin "S6") (pinfunction "S_S6") (pintype "bidirectional"))
      (node (ref "FET6") (pin "S7") (pinfunction "S_S7") (pintype "bidirectional"))
      (node (ref "FET6") (pin "S8") (pinfunction "S_S8") (pintype "bidirectional"))
      (node (ref "IC6") (pin "P$5") (pinfunction "IP+_P$5") (pintype "bidirectional"))
      (node (ref "R12") (pin "P$2") (pinfunction "2_P$2") (pintype "passive"))
    )
    (net (code "39") (name "Net-(IC6-VCC)") (class "Default")
      (node (ref "DC6") (pin "P$1") (pinfunction "P$1_P$1") (pintype "bidirectional"))
      (node (ref "IC6") (pin "P$1") (pinfunction "VCC_P$1") (pintype "bidirectional"))
    )
    (net (code "40") (name "Net-(R1-1)") (class "Default")
      (node (ref "FET1") (pin "G") (pinfunction "G_G") (pintype "bidirectional"))
      (node (ref "R1") (pin "P$1") (pinfunction "1_P$1") (pintype "passive"))
      (node (ref "R9") (pin "P$1") (pinfunction "1_P$1") (pintype "passive"))
    )
    (net (code "41") (name "Net-(R10-1)") (class "Default")
      (node (ref "FET3") (pin "G") (pinfunction "G_G") (pintype "bidirectional"))
      (node (ref "R10") (pin "P$1") (pinfunction "1_P$1") (pintype "passive"))
      (node (ref "R2") (pin "P$1") (pinfunction "1_P$1") (pintype "passive"))
    )
    (net (code "42") (name "Net-(R11-1)") (class "Default")
      (node (ref "FET5") (pin "G") (pinfunction "G_G") (pintype "bidirectional"))
      (node (ref "R11") (pin "P$1") (pinfunction "1_P$1") (pintype "passive"))
      (node (ref "R3") (pin "P$1") (pinfunction "1_P$1") (pintype "passive"))
    )
    (net (code "43") (name "Net-(R12-1)") (class "Default")
      (node (ref "FET6") (pin "G") (pinfunction "G_G") (pintype "bidirectional"))
      (node (ref "R12") (pin "P$1") (pinfunction "1_P$1") (pintype "passive"))
      (node (ref "R4") (pin "P$1") (pinfunction "1_P$1") (pintype "passive"))
    )
    (net (code "44") (name "Net-(R13-1)") (class "Default")
      (node (ref "FET4") (pin "G") (pinfunction "G_G") (pintype "bidirectional"))
      (node (ref "R13") (pin "P$1") (pinfunction "1_P$1") (pintype "passive"))
      (node (ref "R5") (pin "P$1") (pinfunction "1_P$1") (pintype "passive"))
    )
    (net (code "45") (name "Net-(R14-1)") (class "Default")
      (node (ref "FET2") (pin "G") (pinfunction "G_G") (pintype "bidirectional"))
      (node (ref "R14") (pin "P$1") (pinfunction "1_P$1") (pintype "passive"))
      (node (ref "R6") (pin "P$1") (pinfunction "1_P$1") (pintype "passive"))
    )
    (net (code "46") (name "VCC") (class "Default")
      (node (ref "C1") (pin "P$1") (pinfunction "1_P$1") (pintype "passive"))
      (node (ref "C16") (pin "P$1") (pinfunction "+_P$1") (pintype "passive"))
      (node (ref "C17") (pin "P$1") (pinfunction "+_P$1") (pintype "passive"))
      (node (ref "C2") (pin "P$1") (pinfunction "1_P$1") (pintype "passive"))
      (node (ref "C3") (pin "P$1") (pinfunction "1_P$1") (pintype "passive"))
      (node (ref "C4") (pin "P$1") (pinfunction "1_P$1") (pintype "passive"))
      (node (ref "C5") (pin "P$1") (pinfunction "1_P$1") (pintype "passive"))
      (node (ref "C6") (pin "P$1") (pinfunction "1_P$1") (pintype "passive"))
      (node (ref "CN3") (pin "P$1") (pinfunction "P$1_P$1") (pintype "bidirectional"))
      (node (ref "DC-DC1") (pin "P$2") (pinfunction "IN_P$2") (pintype "bidirectional"))
      (node (ref "FD1") (pin "K") (pinfunction "C_K") (pintype "passive"))
      (node (ref "FD3") (pin "K") (pinfunction "C_K") (pintype "passive"))
      (node (ref "FD5") (pin "K") (pinfunction "C_K") (pintype "passive"))
      (node (ref "FET1") (pin "D1") (pinfunction "D_D1") (pintype "bidirectional"))
      (node (ref "FET1") (pin "D2") (pinfunction "D_D2") (pintype "bidirectional"))
      (node (ref "FET1") (pin "D3") (pinfunction "D_D3") (pintype "bidirectional"))
      (node (ref "FET1") (pin "D4") (pinfunction "D_D4") (pintype "bidirectional"))
      (node (ref "FET1") (pin "D5") (pinfunction "D_D5") (pintype "bidirectional"))
      (node (ref "FET1") (pin "D6") (pinfunction "D_D6") (pintype "bidirectional"))
      (node (ref "FET3") (pin "D1") (pinfunction "D_D1") (pintype "bidirectional"))
      (node (ref "FET3") (pin "D2") (pinfunction "D_D2") (pintype "bidirectional"))
      (node (ref "FET3") (pin "D3") (pinfunction "D_D3") (pintype "bidirectional"))
      (node (ref "FET3") (pin "D4") (pinfunction "D_D4") (pintype "bidirectional"))
      (node (ref "FET3") (pin "D5") (pinfunction "D_D5") (pintype "bidirectional"))
      (node (ref "FET3") (pin "D6") (pinfunction "D_D6") (pintype "bidirectional"))
      (node (ref "FET5") (pin "D1") (pinfunction "D_D1") (pintype "bidirectional"))
      (node (ref "FET5") (pin "D2") (pinfunction "D_D2") (pintype "bidirectional"))
      (node (ref "FET5") (pin "D3") (pinfunction "D_D3") (pintype "bidirectional"))
      (node (ref "FET5") (pin "D4") (pinfunction "D_D4") (pintype "bidirectional"))
      (node (ref "FET5") (pin "D5") (pinfunction "D_D5") (pintype "bidirectional"))
      (node (ref "FET5") (pin "D6") (pinfunction "D_D6") (pintype "bidirectional"))
      (node (ref "PMC1") (pin "P$1") (pinfunction "1_P$1") (pintype "passive"))
      (node (ref "PMC2") (pin "P$1") (pinfunction "1_P$1") (pintype "passive"))
      (node (ref "PMC3") (pin "P$1") (pinfunction "1_P$1") (pintype "passive"))
    )
    (net (code "47") (name "unconnected-(CN1-9-PadP$9)") (class "Default")
      (node (ref "CN1") (pin "P$9") (pinfunction "9_P$9") (pintype "passive"))
    )
    (net (code "48") (name "unconnected-(CN1-10-PadP$10)") (class "Default")
      (node (ref "CN1") (pin "P$10") (pinfunction "10_P$10") (pintype "passive"))
    )
    (net (code "49") (name "unconnected-(CN1-11-PadP$11)") (class "Default")
      (node (ref "CN1") (pin "P$11") (pinfunction "11_P$11") (pintype "passive"))
    )
    (net (code "50") (name "unconnected-(CN2-PadP$4)") (class "Default")
      (node (ref "CN2") (pin "P$4") (pinfunction "P$4_P$4") (pintype "bidirectional"))
    )
    (net (code "51") (name "unconnected-(IC2-NC-Pad9)") (class "Default")
      (node (ref "IC2") (pin "9") (pinfunction "NC_9") (pintype "no_connect"))
    )
    (net (code "52") (name "unconnected-(IC2-NC_2-Pad4)") (class "Default")
      (node (ref "IC2") (pin "4") (pinfunction "NC_2_4") (pintype "passive"))
    )
    (net (code "53") (name "unconnected-(IC2-NC_3-Pad10)") (class "Default")
      (node (ref "IC2") (pin "10") (pinfunction "NC_3_10") (pintype "passive"))
    )
    (net (code "54") (name "unconnected-(IC2-NC_4-Pad16)") (class "Default")
      (node (ref "IC2") (pin "16") (pinfunction "NC_4_16") (pintype "passive"))
    )
    (net (code "55") (name "unconnected-(IC2-NC_5-Pad5)") (class "Default")
      (node (ref "IC2") (pin "5") (pinfunction "NC_5_5") (pintype "passive"))
    )
    (net (code "56") (name "unconnected-(IC3-NC-Pad9)") (class "Default")
      (node (ref "IC3") (pin "9") (pinfunction "NC_9") (pintype "no_connect"))
    )
    (net (code "57") (name "unconnected-(IC3-NC_2-Pad4)") (class "Default")
      (node (ref "IC3") (pin "4") (pinfunction "NC_2_4") (pintype "passive"))
    )
    (net (code "58") (name "unconnected-(IC3-NC_3-Pad10)") (class "Default")
      (node (ref "IC3") (pin "10") (pinfunction "NC_3_10") (pintype "passive"))
    )
    (net (code "59") (name "unconnected-(IC3-NC_4-Pad16)") (class "Default")
      (node (ref "IC3") (pin "16") (pinfunction "NC_4_16") (pintype "passive"))
    )
    (net (code "60") (name "unconnected-(IC3-NC_5-Pad5)") (class "Default")
      (node (ref "IC3") (pin "5") (pinfunction "NC_5_5") (pintype "passive"))
    )
    (net (code "61") (name "unconnected-(IC4-NC-Pad9)") (class "Default")
      (node (ref "IC4") (pin "9") (pinfunction "NC_9") (pintype "no_connect"))
    )
    (net (code "62") (name "unconnected-(IC4-NC_2-Pad4)") (class "Default")
      (node (ref "IC4") (pin "4") (pinfunction "NC_2_4") (pintype "passive"))
    )
    (net (code "63") (name "unconnected-(IC4-NC_3-Pad10)") (class "Default")
      (node (ref "IC4") (pin "10") (pinfunction "NC_3_10") (pintype "passive"))
    )
    (net (code "64") (name "unconnected-(IC4-NC_4-Pad16)") (class "Default")
      (node (ref "IC4") (pin "16") (pinfunction "NC_4_16") (pintype "passive"))
    )
    (net (code "65") (name "unconnected-(IC4-NC_5-Pad5)") (class "Default")
      (node (ref "IC4") (pin "5") (pinfunction "NC_5_5") (pintype "passive"))
    )
  )
)
